# TIDA-01592_Power_Supply3.net
KiCad netlist of a schematic drawn in Altium Designer
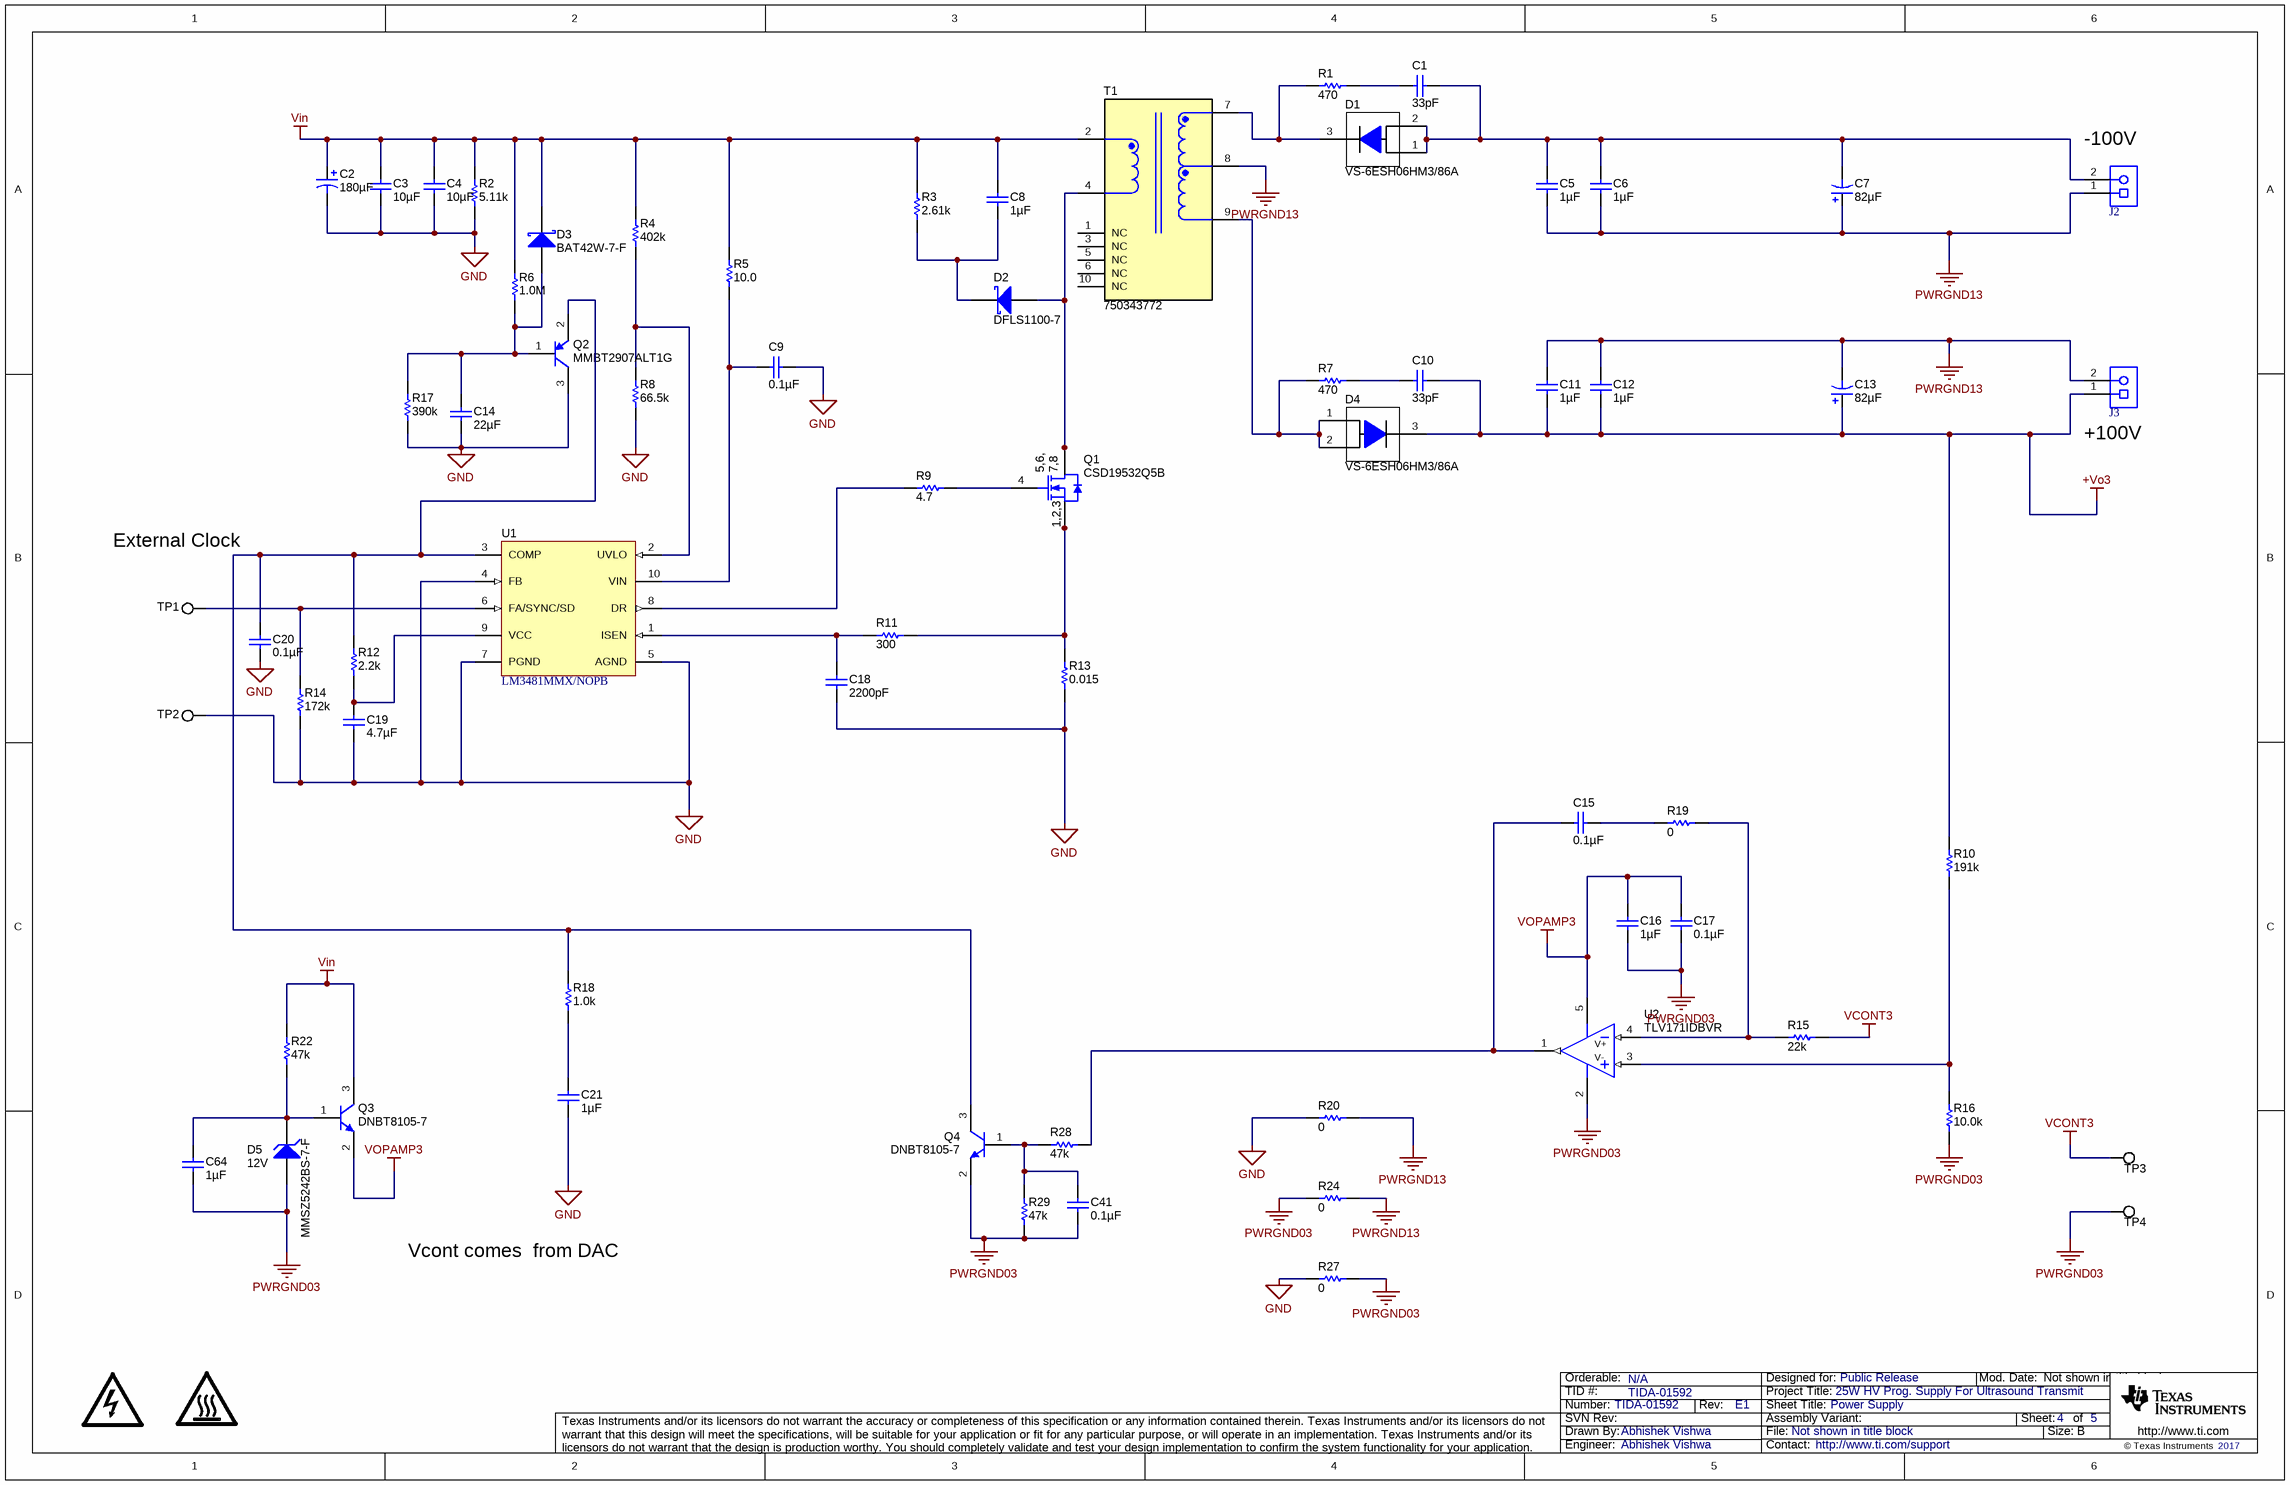
[diagram p0: TIDA-01592_Power Supply3.SchDoc]

(export (version "E")
  (design (tool "Eeschema 10.0.6"))
  (components
    (comp (ref "C1")
      (value "12067A330JAT2A")
      (footprint "1206")
      (description "CAP, CERM, 33 pF, 500 V,+/- 5%, C0G/NP0, 1206")
      (fields
        (field (name "VALUEDISPLAYED") "33pF")
        (field (name "MANUFACTURER") "AVX")
        (field (name "PUBLISHER") "Texas Instruments")
      )
      (libsource (lib "Capacitor_Ceramic") (part "12067A330JAT2A"))
    )
    (comp (ref "C2")
      (value "35TXW180MEFC6.3X25")
      (footprint "FC_630x1120")
      (description "CAP, AL, 180 µF, 35 V, +/- 20%, TH")
      (fields
        (field (name "VALUEDISPLAYED") "180µF")
        (field (name "MANUFACTURER") "Rubycon")
        (field (name "PUBLISHER") "Texas Instruments")
      )
      (libsource (lib "Capacitor_Aluminum") (part "EEU-FC1V470"))
    )
    (comp (ref "C3")
      (value "GRM31CR61H106KA12L")
      (footprint "1206_180")
      (description "CAP, CERM, 10 µF, 50 V,+/- 10%, X5R, 1206")
      (fields
        (field (name "VALUEDISPLAYED") "10µF")
        (field (name "MANUFACTURER") "MuRata")
        (field (name "PUBLISHER") "Texas Instruments")
      )
      (libsource (lib "Capacitor_Ceramic") (part "GRM31CR61H106KA12L"))
    )
    (comp (ref "C4")
      (value "GRM31CR61H106KA12L")
      (footprint "1206_180")
      (description "CAP, CERM, 10 µF, 50 V,+/- 10%, X5R, 1206")
      (fields
        (field (name "VALUEDISPLAYED") "10µF")
        (field (name "MANUFACTURER") "MuRata")
        (field (name "PUBLISHER") "Texas Instruments")
      )
      (libsource (lib "Capacitor_Ceramic") (part "GRM31CR61H106KA12L"))
    )
    (comp (ref "C5")
      (value "C4532X7T2E105M250KE")
      (footprint "1812_180")
      (description "CAP, CERM, 1 µF, 250 V,+/- 20%, X7T, 1812")
      (fields
        (field (name "VALUEDISPLAYED") "1µF")
        (field (name "MANUFACTURER") "TDK Corporation")
        (field (name "PUBLISHER") "Texas Instruments")
      )
      (libsource (lib "Capacitor_Ceramic") (part "C4532X7R1H105K160KA"))
    )
    (comp (ref "C6")
      (value "C4532X7T2E105M250KE")
      (footprint "1812_180")
      (description "CAP, CERM, 1 µF, 250 V,+/- 20%, X7T, 1812")
      (fields
        (field (name "VALUEDISPLAYED") "1µF")
        (field (name "MANUFACTURER") "TDK Corporation")
        (field (name "PUBLISHER") "Texas Instruments")
      )
      (libsource (lib "Capacitor_Ceramic") (part "C4532X7R1H105K160KA"))
    )
    (comp (ref "C7")
      (value "UCY2C820MPD9")
      (footprint "NHG_1000x2000")
      (description "CAP, AL, 82 µF, 160 V, +/- 20%, TH")
      (fields
        (field (name "VALUEDISPLAYED") "82µF")
        (field (name "MANUFACTURER") "Nichicon")
        (field (name "PUBLISHER") "Texas Instruments")
      )
      (libsource (lib "Capacitor_Aluminum") (part "ECA-2AHG101"))
    )
    (comp (ref "C8")
      (value "GRM31CR72A105KA01L")
      (footprint "1206_180")
      (description "CAP, CERM, 1 µF, 100 V,+/- 10%, X7R, 1206")
      (fields
        (field (name "VALUEDISPLAYED") "1µF")
        (field (name "MANUFACTURER") "MuRata")
        (field (name "PUBLISHER") "Texas Instruments")
      )
      (libsource (lib "Capacitor_Ceramic") (part "GRM31CR72A105KA01L"))
    )
    (comp (ref "C9")
      (value "GRM188R71H104KA93D")
      (footprint "0603")
      (description "CAP, CERM, 0.1 µF, 50 V,+/- 10%, X7R, 0603")
      (fields
        (field (name "VALUEDISPLAYED") "0.1µF")
        (field (name "MANUFACTURER") "MuRata")
        (field (name "PUBLISHER") "Texas Instruments")
      )
      (libsource (lib "Capacitor_Ceramic") (part "GRM188R71H104KA93D"))
    )
    (comp (ref "C10")
      (value "12067A330JAT2A")
      (footprint "1206")
      (description "CAP, CERM, 33 pF, 500 V,+/- 5%, C0G/NP0, 1206")
      (fields
        (field (name "VALUEDISPLAYED") "33pF")
        (field (name "MANUFACTURER") "AVX")
        (field (name "PUBLISHER") "Texas Instruments")
      )
      (libsource (lib "Capacitor_Ceramic") (part "12067A330JAT2A"))
    )
    (comp (ref "C11")
      (value "C4532X7T2E105M250KE")
      (footprint "1812_180")
      (description "CAP, CERM, 1 µF, 250 V,+/- 20%, X7T, 1812")
      (fields
        (field (name "VALUEDISPLAYED") "1µF")
        (field (name "MANUFACTURER") "TDK Corporation")
        (field (name "PUBLISHER") "Texas Instruments")
      )
      (libsource (lib "Capacitor_Ceramic") (part "C4532X7R1H105K160KA"))
    )
    (comp (ref "C12")
      (value "C4532X7T2E105M250KE")
      (footprint "1812_180")
      (description "CAP, CERM, 1 µF, 250 V,+/- 20%, X7T, 1812")
      (fields
        (field (name "VALUEDISPLAYED") "1µF")
        (field (name "MANUFACTURER") "TDK Corporation")
        (field (name "PUBLISHER") "Texas Instruments")
      )
      (libsource (lib "Capacitor_Ceramic") (part "C4532X7R1H105K160KA"))
    )
    (comp (ref "C13")
      (value "UCY2C820MPD9")
      (footprint "NHG_1000x2000")
      (description "CAP, AL, 82 µF, 160 V, +/- 20%, TH")
      (fields
        (field (name "VALUEDISPLAYED") "82µF")
        (field (name "MANUFACTURER") "Nichicon")
        (field (name "PUBLISHER") "Texas Instruments")
      )
      (libsource (lib "Capacitor_Aluminum") (part "ECA-2AHG101"))
    )
    (comp (ref "C14")
      (value "C2012X5R1V226M125AC")
      (footprint "0805_HV1")
      (description "CAP, CERM, 22 µF, 35 V,+/- 20%, X5R, 0805")
      (fields
        (field (name "VALUEDISPLAYED") "22µF")
        (field (name "MANUFACTURER") "TDK Corporation")
        (field (name "PUBLISHER") "Texas Instruments")
      )
      (libsource (lib "Capacitor_Ceramic") (part "GRM21BC81C226ME44L"))
    )
    (comp (ref "C15")
      (value "GRM188R71H104KA93D")
      (footprint "0603")
      (description "CAP, CERM, 0.1 µF, 50 V,+/- 10%, X7R, 0603")
      (fields
        (field (name "VALUEDISPLAYED") "0.1µF")
        (field (name "MANUFACTURER") "MuRata")
        (field (name "PUBLISHER") "Texas Instruments")
      )
      (libsource (lib "Capacitor_Ceramic") (part "GRM188R71H104KA93D"))
    )
    (comp (ref "C16")
      (value "UMK107AB7105KA-T")
      (footprint "0603")
      (description "CAP, CERM, 1 µF, 50 V,+/- 10%, X7R, 0603")
      (fields
        (field (name "VALUEDISPLAYED") "1µF")
        (field (name "MANUFACTURER") "Taiyo Yuden")
        (field (name "PUBLISHER") "Texas Instruments")
      )
      (libsource (lib "Capacitor_Ceramic") (part "UMK107AB7105KA-T"))
    )
    (comp (ref "C17")
      (value "GRM188R71H104KA93D")
      (footprint "0603")
      (description "CAP, CERM, 0.1 µF, 50 V,+/- 10%, X7R, 0603")
      (fields
        (field (name "VALUEDISPLAYED") "0.1µF")
        (field (name "MANUFACTURER") "MuRata")
        (field (name "PUBLISHER") "Texas Instruments")
      )
      (libsource (lib "Capacitor_Ceramic") (part "GRM188R71H104KA93D"))
    )
    (comp (ref "C18")
      (value "GRM155R61H222KA01D")
      (footprint "0402")
      (description "CAP, CERM, 2200 pF, 50 V,+/- 10%, X5R, 0402")
      (fields
        (field (name "VALUEDISPLAYED") "2200pF")
        (field (name "MANUFACTURER") "MuRata")
        (field (name "PUBLISHER") "Texas Instruments")
      )
      (libsource (lib "Capacitor_Ceramic") (part "GRM155R61H222KA01D"))
    )
    (comp (ref "C19")
      (value "0603ZD475KAT2A")
      (footprint "0603")
      (description "CAP, CERM, 4.7 µF, 10 V,+/- 10%, X5R, 0603")
      (fields
        (field (name "VALUEDISPLAYED") "4.7µF")
        (field (name "MANUFACTURER") "AVX")
        (field (name "PUBLISHER") "Texas Instruments")
      )
      (libsource (lib "Capacitor_Ceramic") (part "0603ZD475KAT2A"))
    )
    (comp (ref "C20")
      (value "GRM188R71H104KA93D")
      (footprint "0603")
      (description "CAP, CERM, 0.1 µF, 50 V,+/- 10%, X7R, 0603")
      (fields
        (field (name "VALUEDISPLAYED") "0.1µF")
        (field (name "MANUFACTURER") "MuRata")
        (field (name "PUBLISHER") "Texas Instruments")
      )
      (libsource (lib "Capacitor_Ceramic") (part "GRM188R71H104KA93D"))
    )
    (comp (ref "C21")
      (value "C0603C105K3RACTU")
      (footprint "0603")
      (description "CAP, CERM, 1 µF, 25 V,+/- 10%, X7R, 0603")
      (fields
        (field (name "VALUEDISPLAYED") "1µF")
        (field (name "MANUFACTURER") "Kemet")
        (field (name "PUBLISHER") "Texas Instruments")
      )
      (libsource (lib "Capacitor_Ceramic") (part "C0603C105K3RACTU"))
    )
    (comp (ref "C41")
      (value "GRM188R71H104KA93D")
      (footprint "0603")
      (description "CAP, CERM, 0.1 µF, 50 V,+/- 10%, X7R, 0603")
      (fields
        (field (name "VALUEDISPLAYED") "0.1µF")
        (field (name "MANUFACTURER") "MuRata")
        (field (name "PUBLISHER") "Texas Instruments")
      )
      (libsource (lib "Capacitor_Ceramic") (part "GRM188R71H104KA93D"))
    )
    (comp (ref "C64")
      (value "C0603C105K3RACTU")
      (footprint "0603")
      (description "CAP, CERM, 1 µF, 25 V,+/- 10%, X7R, 0603")
      (fields
        (field (name "VALUEDISPLAYED") "1µF")
        (field (name "MANUFACTURER") "Kemet")
        (field (name "PUBLISHER") "Texas Instruments")
      )
      (libsource (lib "Capacitor_Ceramic") (part "C0603C105K3RACTU"))
    )
    (comp (ref "D1")
      (value "VS-6ESH06HM3/86A")
      (footprint "TO-277A")
      (description "Diode, Hyperfast, 600 V, 6 A, AEC-Q101, TO-277A")
      (fields
        (field (name "MANUFACTURER") "Vishay-Semiconductor")
        (field (name "SYMBOLCREATOR") "a0412235")
        (field (name "PUBLISHER") "Texas Instruments")
      )
      (libsource (lib "Diode") (part "VS-6ESH06HM3/86A"))
    )
    (comp (ref "D2")
      (value "DFLS1100-7")
      (footprint "PowerDI123")
      (description "Diode, Schottky, 100 V, 1 A, PowerDI123")
      (fields (field (name "MANUFACTURER") "Diodes Inc.") (field (name "PUBLISHER") "Texas Instruments"))
      (libsource (lib "Diode") (part "DFLS1100-7"))
    )
    (comp (ref "D3")
      (value "BAT42W-7-F")
      (footprint "SOD-123")
      (description "Diode, Schottky, 30 V, 0.2 A, SOD-123")
      (fields (field (name "MANUFACTURER") "Diodes Inc.") (field (name "PUBLISHER") "Texas Instruments"))
      (libsource (lib "Diode") (part "BAT42W-7-F"))
    )
    (comp (ref "D4")
      (value "VS-6ESH06HM3/86A")
      (footprint "TO-277A")
      (description "Diode, Hyperfast, 600 V, 6 A, AEC-Q101, TO-277A")
      (fields
        (field (name "MANUFACTURER") "Vishay-Semiconductor")
        (field (name "SYMBOLCREATOR") "a0412235")
        (field (name "PUBLISHER") "Texas Instruments")
      )
      (libsource (lib "") (part "VS-6ESH06HM3/86A_1"))
    )
    (comp (ref "D5")
      (value "MMSZ5242BS-7-F")
      (footprint "SOD-323")
      (description "Diode, Zener, 12 V, 200 mW, SOD-323")
      (fields
        (field (name "ALTIUM_VALUE") "12V")
        (field (name "MANUFACTURER") "Diodes Inc.")
        (field (name "SYMBOLCREATOR") "a0412235")
        (field (name "PUBLISHER") "Texas Instruments")
      )
      (libsource (lib "ZenerDiodes") (part "MMSZ5242BS-7-F"))
    )
    (comp (ref "J2")
      (value "1727010")
      (footprint "PhoenixConact_1727010")
      (description "Conn Term Block, 2POS, 3.81mm, TH")
      (fields
        (field (name "MANUFACTURER") "Phoenix Contact")
        (field (name "SYMBOLCREATOR") "a0412235")
        (field (name "PUBLISHER") "Texas Instruments")
      )
      (libsource (lib "Connectors_Phoenix_Contact") (part "1727010"))
    )
    (comp (ref "J3")
      (value "1727010")
      (footprint "PhoenixConact_1727010")
      (description "Conn Term Block, 2POS, 3.81mm, TH")
      (fields
        (field (name "MANUFACTURER") "Phoenix Contact")
        (field (name "SYMBOLCREATOR") "a0412235")
        (field (name "PUBLISHER") "Texas Instruments")
      )
      (libsource (lib "Connectors_Phoenix_Contact") (part "1727010"))
    )
    (comp (ref "Q1")
      (value "CSD19532Q5B")
      (footprint "DNK0008A")
      (description "MOSFET, N-CH, 100 V, 17 A, DNK0008A (VSON-CLIP-8)")
      (fields
        (field (name "MANUFACTURER") "Texas Instruments")
        (field (name "PUBLISHER") "Texas Instruments")
      )
      (libsource (lib "FETs") (part "CSD19532Q5B"))
    )
    (comp (ref "Q2")
      (value "MMBT2907ALT1G")
      (footprint "SOT-23")
      (description "Transistor, PNP, 60 V, 0.6 A, SOT-23")
      (fields (field (name "MANUFACTURER") "ON Semiconductor") (field (name "PUBLISHER") "Texas Instruments"))
      (libsource (lib "Bipolar_Transistor") (part "MMBT2907ALT1G, ON Semiconductor"))
    )
    (comp (ref "Q3")
      (value "DNBT8105-7")
      (footprint "SOT-23")
      (description "Transistor, NPN, 60 V, 1 A, AEC-Q101, SOT-23")
      (fields (field (name "MANUFACTURER") "Diodes Inc.") (field (name "PUBLISHER") "Texas Instruments"))
      (libsource (lib "Bipolar_Transistor") (part "DNBT8105-7, Diodes Inc."))
    )
    (comp (ref "Q4")
      (value "DNBT8105-7")
      (footprint "SOT-23")
      (description "Transistor, NPN, 60 V, 1 A, AEC-Q101, SOT-23")
      (fields (field (name "MANUFACTURER") "Diodes Inc.") (field (name "PUBLISHER") "Texas Instruments"))
      (libsource (lib "Bipolar_Transistor") (part "DNBT8105-7, Diodes Inc."))
    )
    (comp (ref "R1")
      (value "CRCW1206470RJNEA")
      (footprint "1206")
      (description "RES, 470, 5%, 0.25 W, 1206")
      (fields
        (field (name "VALUEDISPLAYED") "470")
        (field (name "MANUFACTURER") "Vishay-Dale")
        (field (name "PUBLISHER") "Texas Instruments")
      )
      (libsource (lib "Resistor_1206") (part "CRCW1206470RJNEA"))
    )
    (comp (ref "R2")
      (value "TNPW06035K11BEEA")
      (footprint "TNPW0603")
      (description "RES, 5.11 k, 0.1%, 0.1 W, AEC-Q200 Grade 1, 0603")
      (fields
        (field (name "VALUEDISPLAYED") "5.11k")
        (field (name "MANUFACTURER") "Vishay-Dale")
        (field (name "PUBLISHER") "Texas Instruments")
      )
      (libsource (lib "Resistor_0603") (part "TNPW06035K11BEEA"))
    )
    (comp (ref "R3")
      (value "CRCW20102K61FKEF")
      (footprint "2010")
      (description "RES, 2.61 k, 1%, 0.75 W, AEC-Q200 Grade 0, 2010")
      (fields
        (field (name "VALUEDISPLAYED") "2.61k")
        (field (name "MANUFACTURER") "Vishay-Dale")
        (field (name "PUBLISHER") "Texas Instruments")
      )
      (libsource (lib "Resistor_2010") (part "CRCW20102K61FKEF"))
    )
    (comp (ref "R4")
      (value "CRCW0603402KFKEA")
      (footprint "0603")
      (description "RES, 402 k, 1%, 0.1 W, 0603")
      (fields
        (field (name "VALUEDISPLAYED") "402k")
        (field (name "MANUFACTURER") "Vishay-Dale")
        (field (name "PUBLISHER") "Texas Instruments")
      )
      (libsource (lib "Resistor_0603") (part "CRCW0603402KFKEA"))
    )
    (comp (ref "R5")
      (value "CRCW060310R0FKEAHP")
      (footprint "0603")
      (description "RES, 10.0, 1%, 0.25 W, 0603")
      (fields
        (field (name "R4") "10.0")
        (field (name "MANUFACTURER") "Vishay-Dale")
        (field (name "PUBLISHER") "Texas Instruments")
      )
      (libsource (lib "Resistor_0603") (part "CRCW060310R0FKEAHP"))
    )
    (comp (ref "R6")
      (value "CRCW06031M00JNEA")
      (footprint "0603")
      (description "RES, 1.0 M, 5%, 0.1 W, 0603")
      (fields
        (field (name "VALUEDISPLAYED") "1.0M")
        (field (name "MANUFACTURER") "Vishay-Dale")
        (field (name "PUBLISHER") "Texas Instruments")
      )
      (libsource (lib "Resistor_0603") (part "CRCW06031M00JNEA"))
    )
    (comp (ref "R7")
      (value "CRCW1206470RJNEA")
      (footprint "1206")
      (description "RES, 470, 5%, 0.25 W, 1206")
      (fields
        (field (name "VALUEDISPLAYED") "470")
        (field (name "MANUFACTURER") "Vishay-Dale")
        (field (name "PUBLISHER") "Texas Instruments")
      )
      (libsource (lib "Resistor_1206") (part "CRCW1206470RJNEA"))
    )
    (comp (ref "R8")
      (value "CRCW060366K5FKEA")
      (footprint "0603")
      (description "RES, 66.5 k, 1%, 0.1 W, 0603")
      (fields
        (field (name "VALUEDISPLAYED") "66.5k")
        (field (name "MANUFACTURER") "Vishay-Dale")
        (field (name "PUBLISHER") "Texas Instruments")
      )
      (libsource (lib "Resistor_0603") (part "CRCW060366K5FKEA"))
    )
    (comp (ref "R9")
      (value "CRCW06034R70JNEA")
      (footprint "0603")
      (description "RES, 4.7, 5%, 0.1 W, 0603")
      (fields
        (field (name "VALUEDISPLAYED") "4.7")
        (field (name "MANUFACTURER") "Vishay-Dale")
        (field (name "PUBLISHER") "Texas Instruments")
      )
      (libsource (lib "Resistor_0603") (part "CRCW06034R70JNEA"))
    )
    (comp (ref "R10")
      (value "CRCW0603191KFKEA")
      (footprint "0603")
      (description "RES, 191 k, 1%, 0.1 W, 0603")
      (fields
        (field (name "VALUEDISPLAYED") "191k")
        (field (name "MANUFACTURER") "Vishay-Dale")
        (field (name "PUBLISHER") "Texas Instruments")
      )
      (libsource (lib "Resistor_0603") (part "CRCW0603191KFKEA"))
    )
    (comp (ref "R11")
      (value "CRCW0603300RJNEA")
      (footprint "0603")
      (description "RES, 300, 5%, 0.1 W, 0603")
      (fields
        (field (name "VALUEDISPLAYED") "300")
        (field (name "MANUFACTURER") "Vishay-Dale")
        (field (name "PUBLISHER") "Texas Instruments")
      )
      (libsource (lib "Resistor_0603") (part "CRCW0603300RJNEA"))
    )
    (comp (ref "R12")
      (value "ERJ-3GEYJ222V")
      (footprint "0603")
      (description "RES, 2.2 k, 5%, 0.1 W, AEC-Q200 Grade 0, 0603")
      (fields
        (field (name "VALUEDISPLAYED") "2.2k")
        (field (name "MANUFACTURER") "Panasonic")
        (field (name "PUBLISHER") "Texas Instruments")
      )
      (libsource (lib "Resistor_0603") (part "ERJ-3GEYJ222V"))
    )
    (comp (ref "R13")
      (value "WSL2010R0150FEA18")
      (footprint "2010")
      (description "RES, 0.015, 1%, 1 W, 2010")
      (fields
        (field (name "VALUEDISPLAYED") "0.015")
        (field (name "MANUFACTURER") "Vishay-Dale")
        (field (name "PUBLISHER") "Texas Instruments")
      )
      (libsource (lib "Resistor_2010") (part "WSL2010R0150FEA18"))
    )
    (comp (ref "R14")
      (value "RT0603DRE07172KL")
      (footprint "0603")
      (description "RES, 172 k, 0.5%, 0.1 W, 0603")
      (fields
        (field (name "VALUEDISPLAYED") "172k")
        (field (name "MANUFACTURER") "Yageo America")
        (field (name "PUBLISHER") "Texas Instruments")
      )
      (libsource (lib "Resistor_0603") (part "RT0603DRE07172KL"))
    )
    (comp (ref "R15")
      (value "CRCW060322K0JNEA")
      (footprint "0603")
      (description "RES, 22 k, 5%, 0.1 W, 0603")
      (fields
        (field (name "VALUEDISPLAYED") "22k")
        (field (name "MANUFACTURER") "Vishay-Dale")
        (field (name "PUBLISHER") "Texas Instruments")
      )
      (libsource (lib "Resistor_0603") (part "CRCW060322K0JNEA"))
    )
    (comp (ref "R16")
      (value "CRCW060310K0FKEA")
      (footprint "0603")
      (description "RES, 10.0 k, 1%, 0.1 W, 0603")
      (fields
        (field (name "VALUEDISPLAYED") "10.0k")
        (field (name "MANUFACTURER") "Vishay-Dale")
        (field (name "PUBLISHER") "Texas Instruments")
      )
      (libsource (lib "Resistor_0603") (part "CRCW060310K0FKEA"))
    )
    (comp (ref "R17")
      (value "CRCW0603390KJNEA")
      (footprint "0603")
      (description "RES, 390 k, 5%, 0.1 W, 0603")
      (fields
        (field (name "VALUEDISPLAYED") "390k")
        (field (name "MANUFACTURER") "Vishay-Dale")
        (field (name "PUBLISHER") "Texas Instruments")
      )
      (libsource (lib "Resistor_0603") (part "CRCW0603390KJNEA"))
    )
    (comp (ref "R18")
      (value "CRCW06031K00JNEA")
      (footprint "0603")
      (description "RES, 1.0 k, 5%, 0.1 W, 0603")
      (fields
        (field (name "VALUEDISPLAYED") "1.0k")
        (field (name "MANUFACTURER") "Vishay-Dale")
        (field (name "PUBLISHER") "Texas Instruments")
      )
      (libsource (lib "Resistor_0603") (part "CRCW06031K00JNEA"))
    )
    (comp (ref "R19")
      (value "CRCW04020000Z0ED")
      (footprint "0402")
      (description "RES, 0, 5%, 0.063 W, 0402")
      (fields
        (field (name "VALUEDISPLAYED") "0")
        (field (name "MANUFACTURER") "Vishay-Dale")
        (field (name "PUBLISHER") "Texas Instruments")
      )
      (libsource (lib "Resistor_0402") (part "CRCW04020000Z0ED"))
    )
    (comp (ref "R20")
      (value "CRCW20100000Z0EF")
      (footprint "2010L")
      (description "RES, 0, 5%, 0.75 W, AEC-Q200 Grade 0, 2010")
      (fields
        (field (name "VALUEDISPLAYED") "0")
        (field (name "MANUFACTURER") "Vishay-Dale")
        (field (name "PUBLISHER") "Texas Instruments")
      )
      (libsource (lib "Resistor_2010") (part "CRCW20100000Z0EF"))
    )
    (comp (ref "R22")
      (value "CRCW120647K0JNEA")
      (footprint "1206")
      (description "RES, 47 k, 5%, 0.25 W, 1206")
      (fields
        (field (name "VALUEDISPLAYED") "47k")
        (field (name "MANUFACTURER") "Vishay-Dale")
        (field (name "PUBLISHER") "Texas Instruments")
      )
      (libsource (lib "Resistor_1206") (part "CRCW120647K0JNEA"))
    )
    (comp (ref "R24")
      (value "CRCW20100000Z0EF")
      (footprint "2010L")
      (description "RES, 0, 5%, 0.75 W, AEC-Q200 Grade 0, 2010")
      (fields
        (field (name "VALUEDISPLAYED") "0")
        (field (name "MANUFACTURER") "Vishay-Dale")
        (field (name "PUBLISHER") "Texas Instruments")
      )
      (libsource (lib "Resistor_2010") (part "CRCW20100000Z0EF"))
    )
    (comp (ref "R27")
      (value "CRCW20100000Z0EF")
      (footprint "2010L")
      (description "RES, 0, 5%, 0.75 W, AEC-Q200 Grade 0, 2010")
      (fields
        (field (name "VALUEDISPLAYED") "0")
        (field (name "MANUFACTURER") "Vishay-Dale")
        (field (name "PUBLISHER") "Texas Instruments")
      )
      (libsource (lib "Resistor_2010") (part "CRCW20100000Z0EF"))
    )
    (comp (ref "R28")
      (value "RC0603JR-0747KL")
      (footprint "0603")
      (description "RES, 47 k, 5%, 0.1 W, 0603")
      (fields
        (field (name "VALUEDISPLAYED") "47k")
        (field (name "MANUFACTURER") "Yageo America")
        (field (name "PUBLISHER") "Texas Instruments")
      )
      (libsource (lib "Resistor_0603") (part "RC0603JR-0747KL"))
    )
    (comp (ref "R29")
      (value "RC0603JR-0747KL")
      (footprint "0603")
      (description "RES, 47 k, 5%, 0.1 W, 0603")
      (fields
        (field (name "VALUEDISPLAYED") "47k")
        (field (name "MANUFACTURER") "Yageo America")
        (field (name "PUBLISHER") "Texas Instruments")
      )
      (libsource (lib "Resistor_0603") (part "RC0603JR-0747KL"))
    )
    (comp (ref "T1")
      (value "750343772")
      (footprint "Wurth_EE16_7_5_5278")
      (description "Transformer, 13 uH, TH")
      (fields (field (name "MANUFACTURER") "Wurth Elektronik"))
      (libsource (lib "Altium Vault - TI") (part "Wurth_750343772"))
    )
    (comp (ref "TP1")
      (value "5002")
      (footprint "Keystone5002")
      (description "Test Point, Miniature, White, TH")
      (fields (field (name "MANUFACTURER") "Keystone") (field (name "PUBLISHER") "Texas Instruments"))
      (libsource (lib "Connectors_Keystone") (part "5002"))
    )
    (comp (ref "TP2")
      (value "5002")
      (footprint "Keystone5002")
      (description "Test Point, Miniature, White, TH")
      (fields (field (name "MANUFACTURER") "Keystone") (field (name "PUBLISHER") "Texas Instruments"))
      (libsource (lib "Connectors_Keystone") (part "5002"))
    )
    (comp (ref "TP3")
      (value "5002")
      (footprint "Keystone5002")
      (description "Test Point, Miniature, White, TH")
      (fields (field (name "MANUFACTURER") "Keystone") (field (name "PUBLISHER") "Texas Instruments"))
      (libsource (lib "Connectors_Keystone") (part "5002"))
    )
    (comp (ref "TP4")
      (value "5002")
      (footprint "Keystone5002")
      (description "Test Point, Miniature, White, TH")
      (fields (field (name "MANUFACTURER") "Keystone") (field (name "PUBLISHER") "Texas Instruments"))
      (libsource (lib "Connectors_Keystone") (part "5002"))
    )
    (comp (ref "U1")
      (value "LM3481MMX/NOPB")
      (footprint "MUB10A_N")
      (description "High Efficiency Low-Side N-Channel Controller for Switching Regulators, 10-pin MSOP, Pb-Free")
      (fields (field (name "MANUFACTURER") "Texas Instruments") (field (name "PUBLISHER") "Altium Limited"))
      (libsource (lib "NSC MiscPower") (part "LM3481MMX/NOPB"))
    )
    (comp (ref "U2")
      (value "TLV171IDBVR")
      (footprint "DBV0005A_N")
      (description "36V, Low-Power, RRO, General-Purpose Operational Amplifier, DBV0005A (SOT-23-5)")
      (fields
        (field (name "ALTERNATE PARTNUMBER") "TLV171IDBVT")
        (field (name "MANUFACTURER") "Texas Instruments")
        (field (name "PUBLISHER") "Texas Instruments")
      )
      (libsource (lib "TI_Pre_Release1") (part "TLV171IDBVR"))
    )
  )
  (nets
    (net (code "1") (name "+Vo3") (class "Default")
      (node (ref "C10") (pin "1") (pinfunction "1_1") (pintype "passive"))
      (node (ref "C11") (pin "2") (pinfunction "2_2") (pintype "passive"))
      (node (ref "C12") (pin "2") (pinfunction "2_2") (pintype "passive"))
      (node (ref "C13") (pin "1") (pinfunction "+_1") (pintype "passive"))
      (node (ref "D4") (pin "3") (pinfunction "K_3") (pintype "passive"))
      (node (ref "J3") (pin "1") (pinfunction "1_1") (pintype "passive"))
      (node (ref "R10") (pin "2") (pinfunction "2_2") (pintype "passive"))
    )
    (net (code "2") (name "GND") (class "Default")
      (node (ref "C14") (pin "2") (pinfunction "2_2") (pintype "passive"))
      (node (ref "C18") (pin "2") (pinfunction "2_2") (pintype "passive"))
      (node (ref "C19") (pin "2") (pinfunction "2_2") (pintype "passive"))
      (node (ref "C2") (pin "2") (pinfunction "-_2") (pintype "passive"))
      (node (ref "C20") (pin "1") (pinfunction "1_1") (pintype "passive"))
      (node (ref "C21") (pin "2") (pinfunction "2_2") (pintype "passive"))
      (node (ref "C3") (pin "2") (pinfunction "2_2") (pintype "passive"))
      (node (ref "C4") (pin "2") (pinfunction "2_2") (pintype "passive"))
      (node (ref "C9") (pin "1") (pinfunction "1_1") (pintype "passive"))
      (node (ref "Q2") (pin "3") (pinfunction "C_3") (pintype "passive"))
      (node (ref "R13") (pin "1") (pinfunction "1_1") (pintype "passive"))
      (node (ref "R14") (pin "1") (pinfunction "1_1") (pintype "passive"))
      (node (ref "R17") (pin "1") (pinfunction "1_1") (pintype "passive"))
      (node (ref "R2") (pin "1") (pinfunction "1_1") (pintype "passive"))
      (node (ref "R20") (pin "1") (pinfunction "1_1") (pintype "passive"))
      (node (ref "R27") (pin "1") (pinfunction "1_1") (pintype "passive"))
      (node (ref "R8") (pin "1") (pinfunction "1_1") (pintype "passive"))
      (node (ref "TP2") (pin "1") (pintype "passive"))
      (node (ref "U1") (pin "4") (pinfunction "FB_4") (pintype "input"))
      (node (ref "U1") (pin "5") (pinfunction "AGND_5") (pintype "power_in"))
      (node (ref "U1") (pin "7") (pinfunction "PGND_7") (pintype "power_in"))
    )
    (net (code "3") (name "Net-(C1-Pad2)") (class "Default")
      (node (ref "C1") (pin "2") (pinfunction "2_2") (pintype "passive"))
      (node (ref "R1") (pin "2") (pinfunction "2_2") (pintype "passive"))
    )
    (net (code "4") (name "Net-(C7--)") (class "Default")
      (node (ref "C1") (pin "1") (pinfunction "1_1") (pintype "passive"))
      (node (ref "C5") (pin "1") (pinfunction "1_1") (pintype "passive"))
      (node (ref "C6") (pin "1") (pinfunction "1_1") (pintype "passive"))
      (node (ref "C7") (pin "2") (pinfunction "-_2") (pintype "passive"))
      (node (ref "D1") (pin "1") (pinfunction "A_1") (pintype "passive"))
      (node (ref "D1") (pin "2") (pinfunction "A_2") (pintype "passive"))
      (node (ref "J2") (pin "2") (pinfunction "2_2") (pintype "passive"))
    )
    (net (code "5") (name "Net-(C10-Pad2)") (class "Default")
      (node (ref "C10") (pin "2") (pinfunction "2_2") (pintype "passive"))
      (node (ref "R7") (pin "2") (pinfunction "2_2") (pintype "passive"))
    )
    (net (code "6") (name "Net-(C15-Pad2)") (class "Default")
      (node (ref "C15") (pin "2") (pinfunction "2_2") (pintype "passive"))
      (node (ref "R19") (pin "1") (pinfunction "1_1") (pintype "passive"))
    )
    (net (code "7") (name "Net-(C21-Pad1)") (class "Default")
      (node (ref "C21") (pin "1") (pinfunction "1_1") (pintype "passive"))
      (node (ref "R18") (pin "1") (pinfunction "1_1") (pintype "passive"))
    )
    (net (code "8") (name "Net-(D1-K)") (class "Default")
      (node (ref "D1") (pin "3") (pinfunction "K_3") (pintype "passive"))
      (node (ref "R1") (pin "1") (pinfunction "1_1") (pintype "passive"))
      (node (ref "T1") (pin "7") (pinfunction "7_7") (pintype "passive"))
    )
    (net (code "9") (name "Net-(D2-A)") (class "Default")
      (node (ref "D2") (pin "2") (pinfunction "A_2") (pintype "passive"))
      (node (ref "Q1") (pin "5") (pinfunction "D_5") (pintype "passive"))
      (node (ref "Q1") (pin "6") (pinfunction "D_6") (pintype "passive"))
      (node (ref "Q1") (pin "7") (pinfunction "D_7") (pintype "passive"))
      (node (ref "Q1") (pin "8") (pinfunction "D_8") (pintype "passive"))
      (node (ref "Q1") (pin "9") (pinfunction "D_9") (pintype "passive"))
      (node (ref "T1") (pin "4") (pinfunction "4_4") (pintype "passive"))
    )
    (net (code "10") (name "Net-(D2-K)") (class "Default")
      (node (ref "C8") (pin "2") (pinfunction "2_2") (pintype "passive"))
      (node (ref "D2") (pin "1") (pinfunction "K_1") (pintype "passive"))
      (node (ref "R3") (pin "1") (pinfunction "1_1") (pintype "passive"))
    )
    (net (code "11") (name "Net-(D3-A)") (class "Default")
      (node (ref "C14") (pin "1") (pinfunction "1_1") (pintype "passive"))
      (node (ref "D3") (pin "2") (pinfunction "A_2") (pintype "passive"))
      (node (ref "Q2") (pin "1") (pinfunction "B_1") (pintype "passive"))
      (node (ref "R17") (pin "2") (pinfunction "2_2") (pintype "passive"))
      (node (ref "R6") (pin "1") (pinfunction "1_1") (pintype "passive"))
    )
    (net (code "12") (name "Net-(D4-A-Pad1)") (class "Default")
      (node (ref "D4") (pin "1") (pinfunction "A_1") (pintype "passive"))
      (node (ref "D4") (pin "2") (pinfunction "A_2") (pintype "passive"))
      (node (ref "R7") (pin "1") (pinfunction "1_1") (pintype "passive"))
      (node (ref "T1") (pin "9") (pinfunction "9_9") (pintype "passive"))
    )
    (net (code "13") (name "Net-(D5-K)") (class "Default")
      (node (ref "C64") (pin "1") (pinfunction "1_1") (pintype "passive"))
      (node (ref "D5") (pin "1") (pinfunction "K_1") (pintype "passive"))
      (node (ref "Q3") (pin "1") (pinfunction "B_1") (pintype "passive"))
      (node (ref "R22") (pin "1") (pinfunction "1_1") (pintype "passive"))
    )
    (net (code "14") (name "Net-(Q1-G)") (class "Default")
      (node (ref "Q1") (pin "4") (pinfunction "G_4") (pintype "passive"))
      (node (ref "R9") (pin "2") (pinfunction "2_2") (pintype "passive"))
    )
    (net (code "15") (name "Net-(Q1-S-Pad1)") (class "Default")
      (node (ref "Q1") (pin "1") (pinfunction "S_1") (pintype "passive"))
      (node (ref "Q1") (pin "2") (pinfunction "S_2") (pintype "passive"))
      (node (ref "Q1") (pin "3") (pinfunction "S_3") (pintype "passive"))
      (node (ref "R11") (pin "2") (pinfunction "2_2") (pintype "passive"))
      (node (ref "R13") (pin "2") (pinfunction "2_2") (pintype "passive"))
    )
    (net (code "16") (name "Net-(Q2-E)") (class "Default")
      (node (ref "C20") (pin "2") (pinfunction "2_2") (pintype "passive"))
      (node (ref "Q2") (pin "2") (pinfunction "E_2") (pintype "passive"))
      (node (ref "Q4") (pin "3") (pinfunction "C_3") (pintype "passive"))
      (node (ref "R12") (pin "1") (pinfunction "1_1") (pintype "passive"))
      (node (ref "R18") (pin "2") (pinfunction "2_2") (pintype "passive"))
      (node (ref "U1") (pin "3") (pinfunction "COMP_3") (pintype "passive"))
    )
    (net (code "17") (name "Net-(Q4-B)") (class "Default")
      (node (ref "C41") (pin "2") (pinfunction "2_2") (pintype "passive"))
      (node (ref "Q4") (pin "1") (pinfunction "B_1") (pintype "passive"))
      (node (ref "R28") (pin "2") (pinfunction "2_2") (pintype "passive"))
      (node (ref "R29") (pin "1") (pinfunction "1_1") (pintype "passive"))
    )
    (net (code "18") (name "Net-(U1-DR)") (class "Default")
      (node (ref "R9") (pin "1") (pinfunction "1_1") (pintype "passive"))
      (node (ref "U1") (pin "8") (pinfunction "DR_8") (pintype "output"))
    )
    (net (code "19") (name "Net-(U1-FA{slash}SYNC{slash}SD)") (class "Default")
      (node (ref "R14") (pin "2") (pinfunction "2_2") (pintype "passive"))
      (node (ref "TP1") (pin "1") (pintype "passive"))
      (node (ref "U1") (pin "6") (pinfunction "FA/SYNC/SD_6") (pintype "input"))
    )
    (net (code "20") (name "Net-(U1-ISEN)") (class "Default")
      (node (ref "C18") (pin "1") (pinfunction "1_1") (pintype "passive"))
      (node (ref "R11") (pin "1") (pinfunction "1_1") (pintype "passive"))
      (node (ref "U1") (pin "1") (pinfunction "ISEN_1") (pintype "input"))
    )
    (net (code "21") (name "Net-(U1-UVLO)") (class "Default")
      (node (ref "R4") (pin "1") (pinfunction "1_1") (pintype "passive"))
      (node (ref "R8") (pin "2") (pinfunction "2_2") (pintype "passive"))
      (node (ref "U1") (pin "2") (pinfunction "UVLO_2") (pintype "input"))
    )
    (net (code "22") (name "Net-(U1-VCC)") (class "Default")
      (node (ref "C19") (pin "1") (pinfunction "1_1") (pintype "passive"))
      (node (ref "R12") (pin "2") (pinfunction "2_2") (pintype "passive"))
      (node (ref "U1") (pin "9") (pinfunction "VCC_9") (pintype "power_in"))
    )
    (net (code "23") (name "Net-(U1-VIN)") (class "Default")
      (node (ref "C9") (pin "2") (pinfunction "2_2") (pintype "passive"))
      (node (ref "R5") (pin "2") (pinfunction "2_2") (pintype "passive"))
      (node (ref "U1") (pin "10") (pinfunction "VIN_10") (pintype "power_in"))
    )
    (net (code "24") (name "Net-(U2-IN+)") (class "Default")
      (node (ref "R10") (pin "1") (pinfunction "1_1") (pintype "passive"))
      (node (ref "R16") (pin "1") (pinfunction "1_1") (pintype "passive"))
      (node (ref "U2") (pin "3") (pinfunction "IN+_3") (pintype "input"))
    )
    (net (code "25") (name "Net-(U2-IN-)") (class "Default")
      (node (ref "R15") (pin "1") (pinfunction "1_1") (pintype "passive"))
      (node (ref "R19") (pin "2") (pinfunction "2_2") (pintype "passive"))
      (node (ref "U2") (pin "4") (pinfunction "IN-_4") (pintype "input"))
    )
    (net (code "26") (name "Net-(U2-OUT)") (class "Default")
      (node (ref "C15") (pin "1") (pinfunction "1_1") (pintype "passive"))
      (node (ref "R28") (pin "1") (pinfunction "1_1") (pintype "passive"))
      (node (ref "U2") (pin "1") (pinfunction "OUT_1") (pintype "output"))
    )
    (net (code "27") (name "PWRGND03") (class "Default")
      (node (ref "C16") (pin "2") (pinfunction "2_2") (pintype "passive"))
      (node (ref "C17") (pin "2") (pinfunction "2_2") (pintype "passive"))
      (node (ref "C41") (pin "1") (pinfunction "1_1") (pintype "passive"))
      (node (ref "C64") (pin "2") (pinfunction "2_2") (pintype "passive"))
      (node (ref "D5") (pin "2") (pinfunction "A_2") (pintype "passive"))
      (node (ref "Q4") (pin "2") (pinfunction "E_2") (pintype "passive"))
      (node (ref "R16") (pin "2") (pinfunction "2_2") (pintype "passive"))
      (node (ref "R24") (pin "1") (pinfunction "1_1") (pintype "passive"))
      (node (ref "R27") (pin "2") (pinfunction "2_2") (pintype "passive"))
      (node (ref "R29") (pin "2") (pinfunction "2_2") (pintype "passive"))
      (node (ref "TP4") (pin "1") (pintype "passive"))
      (node (ref "U2") (pin "2") (pinfunction "V-_2") (pintype "power_in"))
    )
    (net (code "28") (name "PWRGND13") (class "Default")
      (node (ref "C11") (pin "1") (pinfunction "1_1") (pintype "passive"))
      (node (ref "C12") (pin "1") (pinfunction "1_1") (pintype "passive"))
      (node (ref "C13") (pin "2") (pinfunction "-_2") (pintype "passive"))
      (node (ref "C5") (pin "2") (pinfunction "2_2") (pintype "passive"))
      (node (ref "C6") (pin "2") (pinfunction "2_2") (pintype "passive"))
      (node (ref "C7") (pin "1") (pinfunction "+_1") (pintype "passive"))
      (node (ref "J2") (pin "1") (pinfunction "1_1") (pintype "passive"))
      (node (ref "J3") (pin "2") (pinfunction "2_2") (pintype "passive"))
      (node (ref "R20") (pin "2") (pinfunction "2_2") (pintype "passive"))
      (node (ref "R24") (pin "2") (pinfunction "2_2") (pintype "passive"))
      (node (ref "T1") (pin "8") (pinfunction "8_8") (pintype "passive"))
    )
    (net (code "29") (name "VCONT3") (class "Default")
      (node (ref "R15") (pin "2") (pinfunction "2_2") (pintype "passive"))
      (node (ref "TP3") (pin "1") (pintype "passive"))
    )
    (net (code "30") (name "VOPAMP3") (class "Default")
      (node (ref "C16") (pin "1") (pinfunction "1_1") (pintype "passive"))
      (node (ref "C17") (pin "1") (pinfunction "1_1") (pintype "passive"))
      (node (ref "Q3") (pin "2") (pinfunction "E_2") (pintype "passive"))
      (node (ref "U2") (pin "5") (pinfunction "V+_5") (pintype "power_in"))
    )
    (net (code "31") (name "Vin") (class "Default")
      (node (ref "C2") (pin "1") (pinfunction "+_1") (pintype "passive"))
      (node (ref "C3") (pin "1") (pinfunction "1_1") (pintype "passive"))
      (node (ref "C4") (pin "1") (pinfunction "1_1") (pintype "passive"))
      (node (ref "C8") (pin "1") (pinfunction "1_1") (pintype "passive"))
      (node (ref "D3") (pin "1") (pinfunction "K_1") (pintype "passive"))
      (node (ref "Q3") (pin "3") (pinfunction "C_3") (pintype "passive"))
      (node (ref "R2") (pin "2") (pinfunction "2_2") (pintype "passive"))
      (node (ref "R22") (pin "2") (pinfunction "2_2") (pintype "passive"))
      (node (ref "R3") (pin "2") (pinfunction "2_2") (pintype "passive"))
      (node (ref "R4") (pin "2") (pinfunction "2_2") (pintype "passive"))
      (node (ref "R5") (pin "1") (pinfunction "1_1") (pintype "passive"))
      (node (ref "R6") (pin "2") (pinfunction "2_2") (pintype "passive"))
      (node (ref "T1") (pin "2") (pinfunction "2_2") (pintype "passive"))
    )
    (net (code "32") (name "unconnected-(T1-NC-Pad1)") (class "Default")
      (node (ref "T1") (pin "1") (pinfunction "NC_1") (pintype "passive"))
    )
    (net (code "33") (name "unconnected-(T1-NC-Pad3)") (class "Default")
      (node (ref "T1") (pin "3") (pinfunction "NC_3") (pintype "passive"))
    )
    (net (code "34") (name "unconnected-(T1-NC-Pad5)") (class "Default")
      (node (ref "T1") (pin "5") (pinfunction "NC_5") (pintype "passive"))
    )
    (net (code "35") (name "unconnected-(T1-NC-Pad6)") (class "Default")
      (node (ref "T1") (pin "6") (pinfunction "NC_6") (pintype "passive"))
    )
    (net (code "36") (name "unconnected-(T1-NC-Pad10)") (class "Default")
      (node (ref "T1") (pin "10") (pinfunction "NC_10") (pintype "passive"))
    )
  )
)
